# 08-DDR3-256MX32.net
KiCad netlist of a schematic drawn in Altium Designer
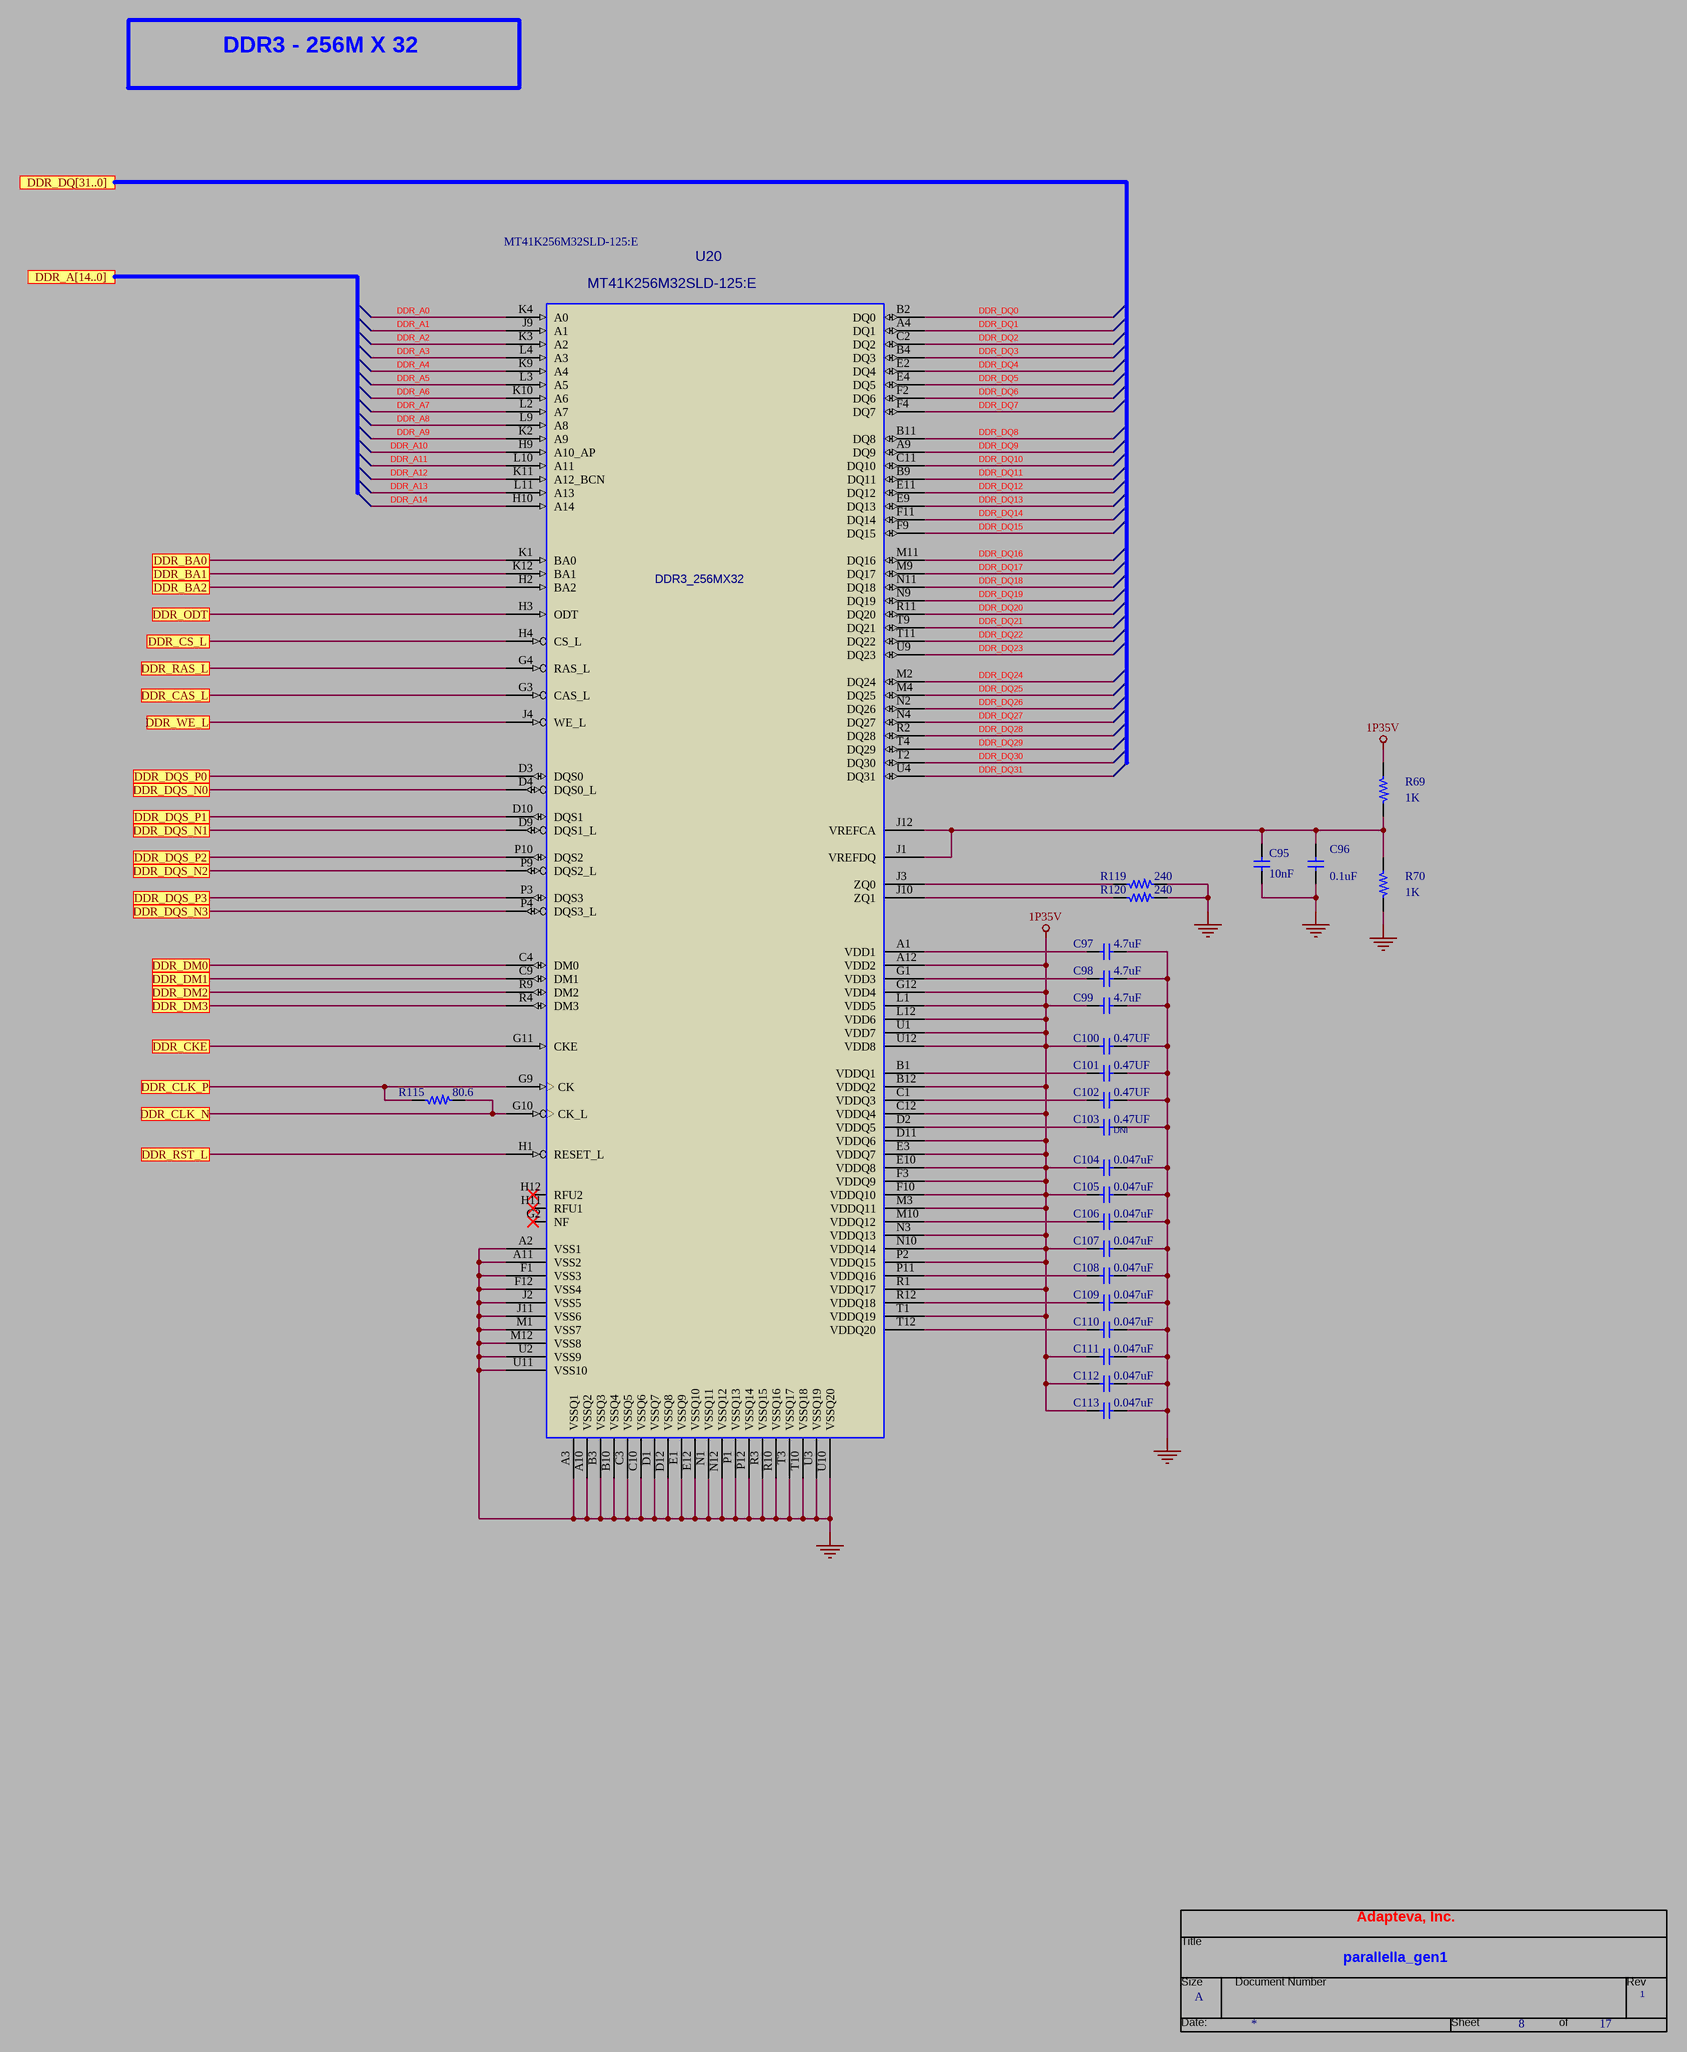
[diagram p0: 08-DDR3-256MX32.SchDoc]

(export (version "E")
  (design (tool "Eeschema 10.0.6"))
  (components
    (comp (ref "C95")
      (value "10nF")
      (footprint "C0402")
      (description "CAP, 0402, 10NF, X7R, 16V")
      (fields (field (name "MFG") "TDK") (field (name "MFG PART NO") "C1005X7R1C103K"))
      (libsource (lib "*") (part "CAP0402_10NF_X7R_16V"))
    )
    (comp (ref "C96")
      (value "0.1uF")
      (footprint "C0402")
      (description "CAP, 0402, 0.1UF, X5R, 35V")
      (fields (field (name "MFG PART NO") "GMK105BJ104KV-F") (field (name "MFG") "TAIYO YUDEN"))
      (libsource (lib "*") (part "CAP0402_0P1UF_X5R_35V"))
    )
    (comp (ref "C97")
      (value "4.7uF")
      (footprint "C0402")
      (description "CAP, 0402, 4.7UF, X5R, 6.3V")
      (fields (field (name "MFG PART NO") "C1005X5R0J475K") (field (name "MFG") "TDK"))
      (libsource (lib "*") (part "CAP0402_4P7UF_X5R"))
    )
    (comp (ref "C98")
      (value "4.7uF")
      (footprint "C0402")
      (description "CAP, 0402, 4.7UF, X5R, 6.3V")
      (fields (field (name "MFG PART NO") "C1005X5R0J475K") (field (name "MFG") "TDK"))
      (libsource (lib "*") (part "CAP0402_4P7UF_X5R"))
    )
    (comp (ref "C99")
      (value "4.7uF")
      (footprint "C0402")
      (description "CAP, 0402, 4.7UF, X5R, 6.3V")
      (fields (field (name "MFG PART NO") "C1005X5R0J475K") (field (name "MFG") "TDK"))
      (libsource (lib "*") (part "CAP0402_4P7UF_X5R"))
    )
    (comp (ref "C100")
      (value "0.47UF")
      (footprint "C0402")
      (description "CAP, 0402, 0.47UF, X5R, 16V")
      (fields (field (name "MFG") "TDK") (field (name "MFG PART NO") "C1005X5R1C474K"))
      (libsource (lib "*") (part "CAP0402_0P47UF_X5R"))
    )
    (comp (ref "C101")
      (value "0.47UF")
      (footprint "C0402")
      (description "CAP, 0402, 0.47UF, X5R, 16V")
      (fields (field (name "MFG") "TDK") (field (name "MFG PART NO") "C1005X5R1C474K"))
      (libsource (lib "*") (part "CAP0402_0P47UF_X5R"))
    )
    (comp (ref "C102")
      (value "0.47UF")
      (footprint "C0402")
      (description "CAP, 0402, 0.47UF, X5R, 16V")
      (fields (field (name "MFG") "TDK") (field (name "MFG PART NO") "C1005X5R1C474K"))
      (libsource (lib "*") (part "CAP0402_0P47UF_X5R"))
    )
    (comp (ref "C103")
      (value "0.47UF")
      (footprint "C0402")
      (description "CAP, 0402, 0.47UF, X5R, 16V")
      (fields
        (field (name "MFG") "TDK")
        (field (name "MFG PART NO") "C1005X5R1C474K")
        (field (name "INSTALL") "DNI")
      )
      (libsource (lib "*") (part "CAP0402_0P47UF_X5R"))
    )
    (comp (ref "C104")
      (value "0.047uF")
      (footprint "C0402")
      (description "CAP, 0402, 0.047UF, X5R, 25V")
      (fields (field (name "MFG") "TDK") (field (name "MFG PART NO") "C1005X5R1E473M"))
      (libsource (lib "*") (part "CAP0402_0P047UF_X5R"))
    )
    (comp (ref "C105")
      (value "0.047uF")
      (footprint "C0402")
      (description "CAP, 0402, 0.047UF, X5R, 25V")
      (fields (field (name "MFG") "TDK") (field (name "MFG PART NO") "C1005X5R1E473M"))
      (libsource (lib "*") (part "CAP0402_0P047UF_X5R"))
    )
    (comp (ref "C106")
      (value "0.047uF")
      (footprint "C0402")
      (description "CAP, 0402, 0.047UF, X5R, 25V")
      (fields (field (name "MFG") "TDK") (field (name "MFG PART NO") "C1005X5R1E473M"))
      (libsource (lib "*") (part "CAP0402_0P047UF_X5R"))
    )
    (comp (ref "C107")
      (value "0.047uF")
      (footprint "C0402")
      (description "CAP, 0402, 0.047UF, X5R, 25V")
      (fields (field (name "MFG") "TDK") (field (name "MFG PART NO") "C1005X5R1E473M"))
      (libsource (lib "*") (part "CAP0402_0P047UF_X5R"))
    )
    (comp (ref "C108")
      (value "0.047uF")
      (footprint "C0402")
      (description "CAP, 0402, 0.047UF, X5R, 25V")
      (fields (field (name "MFG") "TDK") (field (name "MFG PART NO") "C1005X5R1E473M"))
      (libsource (lib "*") (part "CAP0402_0P047UF_X5R"))
    )
    (comp (ref "C109")
      (value "0.047uF")
      (footprint "C0402")
      (description "CAP, 0402, 0.047UF, X5R, 25V")
      (fields (field (name "MFG") "TDK") (field (name "MFG PART NO") "C1005X5R1E473M"))
      (libsource (lib "*") (part "CAP0402_0P047UF_X5R"))
    )
    (comp (ref "C110")
      (value "0.047uF")
      (footprint "C0402")
      (description "CAP, 0402, 0.047UF, X5R, 25V")
      (fields (field (name "MFG") "TDK") (field (name "MFG PART NO") "C1005X5R1E473M"))
      (libsource (lib "*") (part "CAP0402_0P047UF_X5R"))
    )
    (comp (ref "C111")
      (value "0.047uF")
      (footprint "C0402")
      (description "CAP, 0402, 0.047UF, X5R, 25V")
      (fields (field (name "MFG") "TDK") (field (name "MFG PART NO") "C1005X5R1E473M"))
      (libsource (lib "*") (part "CAP0402_0P047UF_X5R"))
    )
    (comp (ref "C112")
      (value "0.047uF")
      (footprint "C0402")
      (description "CAP, 0402, 0.047UF, X5R, 25V")
      (fields (field (name "MFG") "TDK") (field (name "MFG PART NO") "C1005X5R1E473M"))
      (libsource (lib "*") (part "CAP0402_0P047UF_X5R"))
    )
    (comp (ref "C113")
      (value "0.047uF")
      (footprint "C0402")
      (description "CAP, 0402, 0.047UF, X5R, 25V")
      (fields (field (name "MFG") "TDK") (field (name "MFG PART NO") "C1005X5R1E473M"))
      (libsource (lib "*") (part "CAP0402_0P047UF_X5R"))
    )
    (comp (ref "R69")
      (value "1K")
      (footprint "R0402")
      (description "RES, 0402, 1K")
      (fields (field (name "MFG") "VISHAY") (field (name "MFG PART NO") "CRCW04021K00FKED"))
      (libsource (lib "*") (part "RES0402_1K"))
    )
    (comp (ref "R70")
      (value "1K")
      (footprint "R0402")
      (description "RES, 0402, 1K")
      (fields (field (name "MFG") "VISHAY") (field (name "MFG PART NO") "CRCW04021K00FKED"))
      (libsource (lib "*") (part "RES0402_1K"))
    )
    (comp (ref "R115")
      (value "80.6")
      (footprint "R0402")
      (description "RES, 0402, 80.6, 1%")
      (fields (field (name "MFG") "VISHAY") (field (name "MFG PART NO") "CRCW040280R6FKED"))
      (libsource (lib "*") (part "RES0402_80P6"))
    )
    (comp (ref "R119")
      (value "240")
      (footprint "R0402")
      (description "RES, 0402, 240, 1%")
      (fields (field (name "MFG") "VISHAY") (field (name "MFG PART NO") "CRCW0402240RFKED"))
      (libsource (lib "*") (part "RES0402_240"))
    )
    (comp (ref "R120")
      (value "240")
      (footprint "R0402")
      (description "RES, 0402, 240, 1%")
      (fields (field (name "MFG") "VISHAY") (field (name "MFG PART NO") "CRCW0402240RFKED"))
      (libsource (lib "*") (part "RES0402_240"))
    )
    (comp (ref "U20")
      (value "DDR3_256MX32")
      (footprint "FBGA136_11X14X1P1_P8MMP")
      (description "IC, DDR3, 8Gb, 256M32, BGA136")
      (fields
        (field (name "VENDOR PN") "MT41K256M32SLD-125:E")
        (field (name "SUPPLIER PART NUMBER 1") "MT41K256M32SLD-125:E")
      )
      (libsource (lib "*") (part "DDR3_256MX32"))
    )
  )
  (nets
    (net (code "1") (name "/DDR_A0") (class "Default")
      (node (ref "U20") (pin "K4") (pinfunction "A0_K4") (pintype "input"))
    )
    (net (code "2") (name "/DDR_A1") (class "Default")
      (node (ref "U20") (pin "J9") (pinfunction "A1_J9") (pintype "input"))
    )
    (net (code "3") (name "/DDR_A2") (class "Default")
      (node (ref "U20") (pin "K3") (pinfunction "A2_K3") (pintype "input"))
    )
    (net (code "4") (name "/DDR_A3") (class "Default")
      (node (ref "U20") (pin "L4") (pinfunction "A3_L4") (pintype "input"))
    )
    (net (code "5") (name "/DDR_A4") (class "Default")
      (node (ref "U20") (pin "K9") (pinfunction "A4_K9") (pintype "input"))
    )
    (net (code "6") (name "/DDR_A5") (class "Default")
      (node (ref "U20") (pin "L3") (pinfunction "A5_L3") (pintype "input"))
    )
    (net (code "7") (name "/DDR_A6") (class "Default")
      (node (ref "U20") (pin "K10") (pinfunction "A6_K10") (pintype "input"))
    )
    (net (code "8") (name "/DDR_A7") (class "Default")
      (node (ref "U20") (pin "L2") (pinfunction "A7_L2") (pintype "input"))
    )
    (net (code "9") (name "/DDR_A8") (class "Default")
      (node (ref "U20") (pin "L9") (pinfunction "A8_L9") (pintype "input"))
    )
    (net (code "10") (name "/DDR_A9") (class "Default")
      (node (ref "U20") (pin "K2") (pinfunction "A9_K2") (pintype "input"))
    )
    (net (code "11") (name "/DDR_A10") (class "Default")
      (node (ref "U20") (pin "H9") (pinfunction "A10_AP_H9") (pintype "input"))
    )
    (net (code "12") (name "/DDR_A11") (class "Default")
      (node (ref "U20") (pin "L10") (pinfunction "A11_L10") (pintype "input"))
    )
    (net (code "13") (name "/DDR_A12") (class "Default")
      (node (ref "U20") (pin "K11") (pinfunction "A12_BCN_K11") (pintype "input"))
    )
    (net (code "14") (name "/DDR_A13") (class "Default")
      (node (ref "U20") (pin "L11") (pinfunction "A13_L11") (pintype "input"))
    )
    (net (code "15") (name "/DDR_A14") (class "Default")
      (node (ref "U20") (pin "H10") (pinfunction "A14_H10") (pintype "input"))
    )
    (net (code "17") (name "/DDR_BA0") (class "Default")
      (node (ref "U20") (pin "K1") (pinfunction "BA0_K1") (pintype "input"))
    )
    (net (code "18") (name "/DDR_BA1") (class "Default")
      (node (ref "U20") (pin "K12") (pinfunction "BA1_K12") (pintype "input"))
    )
    (net (code "19") (name "/DDR_BA2") (class "Default")
      (node (ref "U20") (pin "H2") (pinfunction "BA2_H2") (pintype "input"))
    )
    (net (code "20") (name "/DDR_CAS_L") (class "Default")
      (node (ref "U20") (pin "G3") (pinfunction "CAS_L_G3") (pintype "input"))
    )
    (net (code "21") (name "/DDR_CKE") (class "Default")
      (node (ref "U20") (pin "G11") (pinfunction "CKE_G11") (pintype "input"))
    )
    (net (code "22") (name "/DDR_CLK_N") (class "Default")
      (node (ref "R115") (pin "2") (pinfunction "2_2") (pintype "passive"))
      (node (ref "U20") (pin "G10") (pinfunction "CK_L_G10") (pintype "input"))
    )
    (net (code "23") (name "/DDR_CLK_P") (class "Default")
      (node (ref "R115") (pin "1") (pinfunction "1_1") (pintype "passive"))
      (node (ref "U20") (pin "G9") (pinfunction "CK_G9") (pintype "input"))
    )
    (net (code "24") (name "/DDR_CS_L") (class "Default")
      (node (ref "U20") (pin "H4") (pinfunction "CS_L_H4") (pintype "input"))
    )
    (net (code "25") (name "/DDR_DM0") (class "Default")
      (node (ref "U20") (pin "C4") (pinfunction "DM0_C4") (pintype "bidirectional"))
    )
    (net (code "26") (name "/DDR_DM1") (class "Default")
      (node (ref "U20") (pin "C9") (pinfunction "DM1_C9") (pintype "bidirectional"))
    )
    (net (code "27") (name "/DDR_DM2") (class "Default")
      (node (ref "U20") (pin "R9") (pinfunction "DM2_R9") (pintype "bidirectional"))
    )
    (net (code "28") (name "/DDR_DM3") (class "Default")
      (node (ref "U20") (pin "R4") (pinfunction "DM3_R4") (pintype "bidirectional"))
    )
    (net (code "29") (name "/DDR_DQ0") (class "Default")
      (node (ref "U20") (pin "B2") (pinfunction "DQ0_B2") (pintype "bidirectional"))
    )
    (net (code "30") (name "/DDR_DQ1") (class "Default")
      (node (ref "U20") (pin "A4") (pinfunction "DQ1_A4") (pintype "bidirectional"))
    )
    (net (code "31") (name "/DDR_DQ2") (class "Default")
      (node (ref "U20") (pin "C2") (pinfunction "DQ2_C2") (pintype "bidirectional"))
    )
    (net (code "32") (name "/DDR_DQ3") (class "Default")
      (node (ref "U20") (pin "B4") (pinfunction "DQ3_B4") (pintype "bidirectional"))
    )
    (net (code "33") (name "/DDR_DQ4") (class "Default")
      (node (ref "U20") (pin "E2") (pinfunction "DQ4_E2") (pintype "bidirectional"))
    )
    (net (code "34") (name "/DDR_DQ5") (class "Default")
      (node (ref "U20") (pin "E4") (pinfunction "DQ5_E4") (pintype "bidirectional"))
    )
    (net (code "35") (name "/DDR_DQ6") (class "Default")
      (node (ref "U20") (pin "F2") (pinfunction "DQ6_F2") (pintype "bidirectional"))
    )
    (net (code "36") (name "/DDR_DQ7") (class "Default")
      (node (ref "U20") (pin "F4") (pinfunction "DQ7_F4") (pintype "bidirectional"))
    )
    (net (code "37") (name "/DDR_DQ8") (class "Default")
      (node (ref "U20") (pin "B11") (pinfunction "DQ8_B11") (pintype "bidirectional"))
    )
    (net (code "38") (name "/DDR_DQ9") (class "Default")
      (node (ref "U20") (pin "A9") (pinfunction "DQ9_A9") (pintype "bidirectional"))
    )
    (net (code "39") (name "/DDR_DQ10") (class "Default")
      (node (ref "U20") (pin "C11") (pinfunction "DQ10_C11") (pintype "bidirectional"))
    )
    (net (code "40") (name "/DDR_DQ11") (class "Default")
      (node (ref "U20") (pin "B9") (pinfunction "DQ11_B9") (pintype "bidirectional"))
    )
    (net (code "41") (name "/DDR_DQ12") (class "Default")
      (node (ref "U20") (pin "E11") (pinfunction "DQ12_E11") (pintype "bidirectional"))
    )
    (net (code "42") (name "/DDR_DQ13") (class "Default")
      (node (ref "U20") (pin "E9") (pinfunction "DQ13_E9") (pintype "bidirectional"))
    )
    (net (code "43") (name "/DDR_DQ14") (class "Default")
      (node (ref "U20") (pin "F11") (pinfunction "DQ14_F11") (pintype "bidirectional"))
    )
    (net (code "44") (name "/DDR_DQ15") (class "Default")
      (node (ref "U20") (pin "F9") (pinfunction "DQ15_F9") (pintype "bidirectional"))
    )
    (net (code "45") (name "/DDR_DQ16") (class "Default")
      (node (ref "U20") (pin "M11") (pinfunction "DQ16_M11") (pintype "bidirectional"))
    )
    (net (code "46") (name "/DDR_DQ17") (class "Default")
      (node (ref "U20") (pin "M9") (pinfunction "DQ17_M9") (pintype "bidirectional"))
    )
    (net (code "47") (name "/DDR_DQ18") (class "Default")
      (node (ref "U20") (pin "N11") (pinfunction "DQ18_N11") (pintype "bidirectional"))
    )
    (net (code "48") (name "/DDR_DQ19") (class "Default")
      (node (ref "U20") (pin "N9") (pinfunction "DQ19_N9") (pintype "bidirectional"))
    )
    (net (code "49") (name "/DDR_DQ20") (class "Default")
      (node (ref "U20") (pin "R11") (pinfunction "DQ20_R11") (pintype "bidirectional"))
    )
    (net (code "50") (name "/DDR_DQ21") (class "Default")
      (node (ref "U20") (pin "T9") (pinfunction "DQ21_T9") (pintype "bidirectional"))
    )
    (net (code "51") (name "/DDR_DQ22") (class "Default")
      (node (ref "U20") (pin "T11") (pinfunction "DQ22_T11") (pintype "bidirectional"))
    )
    (net (code "52") (name "/DDR_DQ23") (class "Default")
      (node (ref "U20") (pin "U9") (pinfunction "DQ23_U9") (pintype "bidirectional"))
    )
    (net (code "53") (name "/DDR_DQ24") (class "Default")
      (node (ref "U20") (pin "M2") (pinfunction "DQ24_M2") (pintype "bidirectional"))
    )
    (net (code "54") (name "/DDR_DQ25") (class "Default")
      (node (ref "U20") (pin "M4") (pinfunction "DQ25_M4") (pintype "bidirectional"))
    )
    (net (code "55") (name "/DDR_DQ26") (class "Default")
      (node (ref "U20") (pin "N2") (pinfunction "DQ26_N2") (pintype "bidirectional"))
    )
    (net (code "56") (name "/DDR_DQ27") (class "Default")
      (node (ref "U20") (pin "N4") (pinfunction "DQ27_N4") (pintype "bidirectional"))
    )
    (net (code "57") (name "/DDR_DQ28") (class "Default")
      (node (ref "U20") (pin "R2") (pinfunction "DQ28_R2") (pintype "bidirectional"))
    )
    (net (code "58") (name "/DDR_DQ29") (class "Default")
      (node (ref "U20") (pin "T4") (pinfunction "DQ29_T4") (pintype "bidirectional"))
    )
    (net (code "59") (name "/DDR_DQ30") (class "Default")
      (node (ref "U20") (pin "T2") (pinfunction "DQ30_T2") (pintype "bidirectional"))
    )
    (net (code "60") (name "/DDR_DQ31") (class "Default")
      (node (ref "U20") (pin "U4") (pinfunction "DQ31_U4") (pintype "bidirectional"))
    )
    (net (code "61") (name "/DDR_DQS_N0") (class "Default")
      (node (ref "U20") (pin "D4") (pinfunction "DQS0_L_D4") (pintype "bidirectional"))
    )
    (net (code "62") (name "/DDR_DQS_N1") (class "Default")
      (node (ref "U20") (pin "D9") (pinfunction "DQS1_L_D9") (pintype "bidirectional"))
    )
    (net (code "63") (name "/DDR_DQS_N2") (class "Default")
      (node (ref "U20") (pin "P9") (pinfunction "DQS2_L_P9") (pintype "bidirectional"))
    )
    (net (code "64") (name "/DDR_DQS_N3") (class "Default")
      (node (ref "U20") (pin "P4") (pinfunction "DQS3_L_P4") (pintype "bidirectional"))
    )
    (net (code "65") (name "/DDR_DQS_P0") (class "Default")
      (node (ref "U20") (pin "D3") (pinfunction "DQS0_D3") (pintype "bidirectional"))
    )
    (net (code "66") (name "/DDR_DQS_P1") (class "Default")
      (node (ref "U20") (pin "D10") (pinfunction "DQS1_D10") (pintype "bidirectional"))
    )
    (net (code "67") (name "/DDR_DQS_P2") (class "Default")
      (node (ref "U20") (pin "P10") (pinfunction "DQS2_P10") (pintype "bidirectional"))
    )
    (net (code "68") (name "/DDR_DQS_P3") (class "Default")
      (node (ref "U20") (pin "P3") (pinfunction "DQS3_P3") (pintype "bidirectional"))
    )
    (net (code "70") (name "/DDR_ODT") (class "Default")
      (node (ref "U20") (pin "H3") (pinfunction "ODT_H3") (pintype "input"))
    )
    (net (code "71") (name "/DDR_RAS_L") (class "Default")
      (node (ref "U20") (pin "G4") (pinfunction "RAS_L_G4") (pintype "input"))
    )
    (net (code "72") (name "/DDR_RST_L") (class "Default")
      (node (ref "U20") (pin "H1") (pinfunction "RESET_L_H1") (pintype "input"))
    )
    (net (code "73") (name "/DDR_WE_L") (class "Default")
      (node (ref "U20") (pin "J4") (pinfunction "WE_L_J4") (pintype "input"))
    )
    (net (code "74") (name "1P35V") (class "Default")
      (node (ref "C100") (pin "1") (pinfunction "1_1") (pintype "passive"))
      (node (ref "C104") (pin "1") (pinfunction "1_1") (pintype "passive"))
      (node (ref "C105") (pin "1") (pinfunction "1_1") (pintype "passive"))
      (node (ref "C107") (pin "1") (pinfunction "1_1") (pintype "passive"))
      (node (ref "C111") (pin "1") (pinfunction "1_1") (pintype "passive"))
      (node (ref "C112") (pin "1") (pinfunction "1_1") (pintype "passive"))
      (node (ref "C113") (pin "1") (pinfunction "1_1") (pintype "passive"))
      (node (ref "C99") (pin "1") (pinfunction "1_1") (pintype "passive"))
      (node (ref "R69") (pin "1") (pinfunction "1_1") (pintype "passive"))
      (node (ref "U20") (pin "A12") (pinfunction "VDD2_A12") (pintype "power_in"))
      (node (ref "U20") (pin "B12") (pinfunction "VDDQ2_B12") (pintype "power_in"))
      (node (ref "U20") (pin "C12") (pinfunction "VDDQ4_C12") (pintype "power_in"))
      (node (ref "U20") (pin "D11") (pinfunction "VDDQ6_D11") (pintype "power_in"))
      (node (ref "U20") (pin "E10") (pinfunction "VDDQ8_E10") (pintype "power_in"))
      (node (ref "U20") (pin "E3") (pinfunction "VDDQ7_E3") (pintype "power_in"))
      (node (ref "U20") (pin "F10") (pinfunction "VDDQ10_F10") (pintype "power_in"))
      (node (ref "U20") (pin "F3") (pinfunction "VDDQ9_F3") (pintype "power_in"))
      (node (ref "U20") (pin "G12") (pinfunction "VDD4_G12") (pintype "power_in"))
      (node (ref "U20") (pin "L1") (pinfunction "VDD5_L1") (pintype "power_in"))
      (node (ref "U20") (pin "L12") (pinfunction "VDD6_L12") (pintype "power_in"))
      (node (ref "U20") (pin "M3") (pinfunction "VDDQ11_M3") (pintype "power_in"))
      (node (ref "U20") (pin "N10") (pinfunction "VDDQ14_N10") (pintype "power_in"))
      (node (ref "U20") (pin "N3") (pinfunction "VDDQ13_N3") (pintype "power_in"))
      (node (ref "U20") (pin "P2") (pinfunction "VDDQ15_P2") (pintype "power_in"))
      (node (ref "U20") (pin "R1") (pinfunction "VDDQ17_R1") (pintype "power_in"))
      (node (ref "U20") (pin "T1") (pinfunction "VDDQ19_T1") (pintype "power_in"))
      (node (ref "U20") (pin "U1") (pinfunction "VDD7_U1") (pintype "power_in"))
      (node (ref "U20") (pin "U12") (pinfunction "VDD8_U12") (pintype "power_in"))
    )
    (net (code "75") (name "GND") (class "Default")
      (node (ref "C100") (pin "2") (pinfunction "2_2") (pintype "passive"))
      (node (ref "C101") (pin "2") (pinfunction "2_2") (pintype "passive"))
      (node (ref "C102") (pin "2") (pinfunction "2_2") (pintype "passive"))
      (node (ref "C103") (pin "2") (pinfunction "2_2") (pintype "passive"))
      (node (ref "C104") (pin "2") (pinfunction "2_2") (pintype "passive"))
      (node (ref "C105") (pin "2") (pinfunction "2_2") (pintype "passive"))
      (node (ref "C106") (pin "2") (pinfunction "2_2") (pintype "passive"))
      (node (ref "C107") (pin "2") (pinfunction "2_2") (pintype "passive"))
      (node (ref "C108") (pin "2") (pinfunction "2_2") (pintype "passive"))
      (node (ref "C109") (pin "2") (pinfunction "2_2") (pintype "passive"))
      (node (ref "C110") (pin "2") (pinfunction "2_2") (pintype "passive"))
      (node (ref "C111") (pin "2") (pinfunction "2_2") (pintype "passive"))
      (node (ref "C112") (pin "2") (pinfunction "2_2") (pintype "passive"))
      (node (ref "C113") (pin "2") (pinfunction "2_2") (pintype "passive"))
      (node (ref "C95") (pin "2") (pinfunction "2_2") (pintype "passive"))
      (node (ref "C96") (pin "1") (pinfunction "1_1") (pintype "passive"))
      (node (ref "C97") (pin "2") (pinfunction "2_2") (pintype "passive"))
      (node (ref "C98") (pin "2") (pinfunction "2_2") (pintype "passive"))
      (node (ref "C99") (pin "2") (pinfunction "2_2") (pintype "passive"))
      (node (ref "R119") (pin "2") (pinfunction "2_2") (pintype "passive"))
      (node (ref "R120") (pin "2") (pinfunction "2_2") (pintype "passive"))
      (node (ref "R70") (pin "2") (pinfunction "2_2") (pintype "passive"))
      (node (ref "U20") (pin "A10") (pinfunction "VSSQ2_A10") (pintype "power_in"))
      (node (ref "U20") (pin "A11") (pinfunction "VSS2_A11") (pintype "power_in"))
      (node (ref "U20") (pin "A2") (pinfunction "VSS1_A2") (pintype "power_in"))
      (node (ref "U20") (pin "A3") (pinfunction "VSSQ1_A3") (pintype "power_in"))
      (node (ref "U20") (pin "B10") (pinfunction "VSSQ4_B10") (pintype "power_in"))
      (node (ref "U20") (pin "B3") (pinfunction "VSSQ3_B3") (pintype "power_in"))
      (node (ref "U20") (pin "C10") (pinfunction "VSSQ6_C10") (pintype "power_in"))
      (node (ref "U20") (pin "C3") (pinfunction "VSSQ5_C3") (pintype "power_in"))
      (node (ref "U20") (pin "D1") (pinfunction "VSSQ7_D1") (pintype "power_in"))
      (node (ref "U20") (pin "D12") (pinfunction "VSSQ8_D12") (pintype "power_in"))
      (node (ref "U20") (pin "E1") (pinfunction "VSSQ9_E1") (pintype "power_in"))
      (node (ref "U20") (pin "E12") (pinfunction "VSSQ10_E12") (pintype "power_in"))
      (node (ref "U20") (pin "F1") (pinfunction "VSS3_F1") (pintype "power_in"))
      (node (ref "U20") (pin "F12") (pinfunction "VSS4_F12") (pintype "power_in"))
      (node (ref "U20") (pin "J11") (pinfunction "VSS6_J11") (pintype "power_in"))
      (node (ref "U20") (pin "J2") (pinfunction "VSS5_J2") (pintype "power_in"))
      (node (ref "U20") (pin "M1") (pinfunction "VSS7_M1") (pintype "power_in"))
      (node (ref "U20") (pin "M12") (pinfunction "VSS8_M12") (pintype "power_in"))
      (node (ref "U20") (pin "N1") (pinfunction "VSSQ11_N1") (pintype "power_in"))
      (node (ref "U20") (pin "N12") (pinfunction "VSSQ12_N12") (pintype "power_in"))
      (node (ref "U20") (pin "P1") (pinfunction "VSSQ13_P1") (pintype "power_in"))
      (node (ref "U20") (pin "P12") (pinfunction "VSSQ14_P12") (pintype "power_in"))
      (node (ref "U20") (pin "R10") (pinfunction "VSSQ16_R10") (pintype "power_in"))
      (node (ref "U20") (pin "R3") (pinfunction "VSSQ15_R3") (pintype "power_in"))
      (node (ref "U20") (pin "T10") (pinfunction "VSSQ18_T10") (pintype "power_in"))
      (node (ref "U20") (pin "T3") (pinfunction "VSSQ17_T3") (pintype "power_in"))
      (node (ref "U20") (pin "U10") (pinfunction "VSSQ20_U10") (pintype "power_in"))
      (node (ref "U20") (pin "U11") (pinfunction "VSS10_U11") (pintype "power_in"))
      (node (ref "U20") (pin "U2") (pinfunction "VSS9_U2") (pintype "power_in"))
      (node (ref "U20") (pin "U3") (pinfunction "VSSQ19_U3") (pintype "power_in"))
    )
    (net (code "76") (name "Net-(U20-VDD1)") (class "Default")
      (node (ref "C97") (pin "1") (pinfunction "1_1") (pintype "passive"))
      (node (ref "U20") (pin "A1") (pinfunction "VDD1_A1") (pintype "power_in"))
    )
    (net (code "77") (name "Net-(U20-VDD3)") (class "Default")
      (node (ref "C98") (pin "1") (pinfunction "1_1") (pintype "passive"))
      (node (ref "U20") (pin "G1") (pinfunction "VDD3_G1") (pintype "power_in"))
    )
    (net (code "78") (name "Net-(U20-VDDQ1)") (class "Default")
      (node (ref "C101") (pin "1") (pinfunction "1_1") (pintype "passive"))
      (node (ref "U20") (pin "B1") (pinfunction "VDDQ1_B1") (pintype "power_in"))
    )
    (net (code "79") (name "Net-(U20-VDDQ3)") (class "Default")
      (node (ref "C102") (pin "1") (pinfunction "1_1") (pintype "passive"))
      (node (ref "U20") (pin "C1") (pinfunction "VDDQ3_C1") (pintype "power_in"))
    )
    (net (code "80") (name "Net-(U20-VDDQ5)") (class "Default")
      (node (ref "C103") (pin "1") (pinfunction "1_1") (pintype "passive"))
      (node (ref "U20") (pin "D2") (pinfunction "VDDQ5_D2") (pintype "power_in"))
    )
    (net (code "81") (name "Net-(U20-VDDQ12)") (class "Default")
      (node (ref "C106") (pin "1") (pinfunction "1_1") (pintype "passive"))
      (node (ref "U20") (pin "M10") (pinfunction "VDDQ12_M10") (pintype "power_in"))
    )
    (net (code "82") (name "Net-(U20-VDDQ16)") (class "Default")
      (node (ref "C108") (pin "1") (pinfunction "1_1") (pintype "passive"))
      (node (ref "U20") (pin "P11") (pinfunction "VDDQ16_P11") (pintype "power_in"))
    )
    (net (code "83") (name "Net-(U20-VDDQ18)") (class "Default")
      (node (ref "C109") (pin "1") (pinfunction "1_1") (pintype "passive"))
      (node (ref "U20") (pin "R12") (pinfunction "VDDQ18_R12") (pintype "power_in"))
    )
    (net (code "84") (name "Net-(U20-VDDQ20)") (class "Default")
      (node (ref "C110") (pin "1") (pinfunction "1_1") (pintype "passive"))
      (node (ref "U20") (pin "T12") (pinfunction "VDDQ20_T12") (pintype "power_in"))
    )
    (net (code "85") (name "Net-(U20-VREFCA)") (class "Default")
      (node (ref "C95") (pin "1") (pinfunction "1_1") (pintype "passive"))
      (node (ref "C96") (pin "2") (pinfunction "2_2") (pintype "passive"))
      (node (ref "R69") (pin "2") (pinfunction "2_2") (pintype "passive"))
      (node (ref "R70") (pin "1") (pinfunction "1_1") (pintype "passive"))
      (node (ref "U20") (pin "J1") (pinfunction "VREFDQ_J1") (pintype "power_in"))
      (node (ref "U20") (pin "J12") (pinfunction "VREFCA_J12") (pintype "power_in"))
    )
    (net (code "86") (name "Net-(U20-ZQ0)") (class "Default")
      (node (ref "R119") (pin "1") (pinfunction "1_1") (pintype "passive"))
      (node (ref "U20") (pin "J3") (pinfunction "ZQ0_J3") (pintype "passive"))
    )
    (net (code "87") (name "Net-(U20-ZQ1)") (class "Default")
      (node (ref "R120") (pin "1") (pinfunction "1_1") (pintype "passive"))
      (node (ref "U20") (pin "J10") (pinfunction "ZQ1_J10") (pintype "passive"))
    )
    (net (code "88") (name "unconnected-(U20-NF-PadG2)") (class "Default")
      (node (ref "U20") (pin "G2") (pinfunction "NF_G2") (pintype "passive+no_connect"))
    )
    (net (code "89") (name "unconnected-(U20-RFU1-PadH11)") (class "Default")
      (node (ref "U20") (pin "H11") (pinfunction "RFU1_H11") (pintype "passive+no_connect"))
    )
    (net (code "90") (name "unconnected-(U20-RFU2-PadH12)") (class "Default")
      (node (ref "U20") (pin "H12") (pinfunction "RFU2_H12") (pintype "passive+no_connect"))
    )
  )
)
